# CAN_IF.net
KiCad netlist of a schematic drawn in Altium Designer
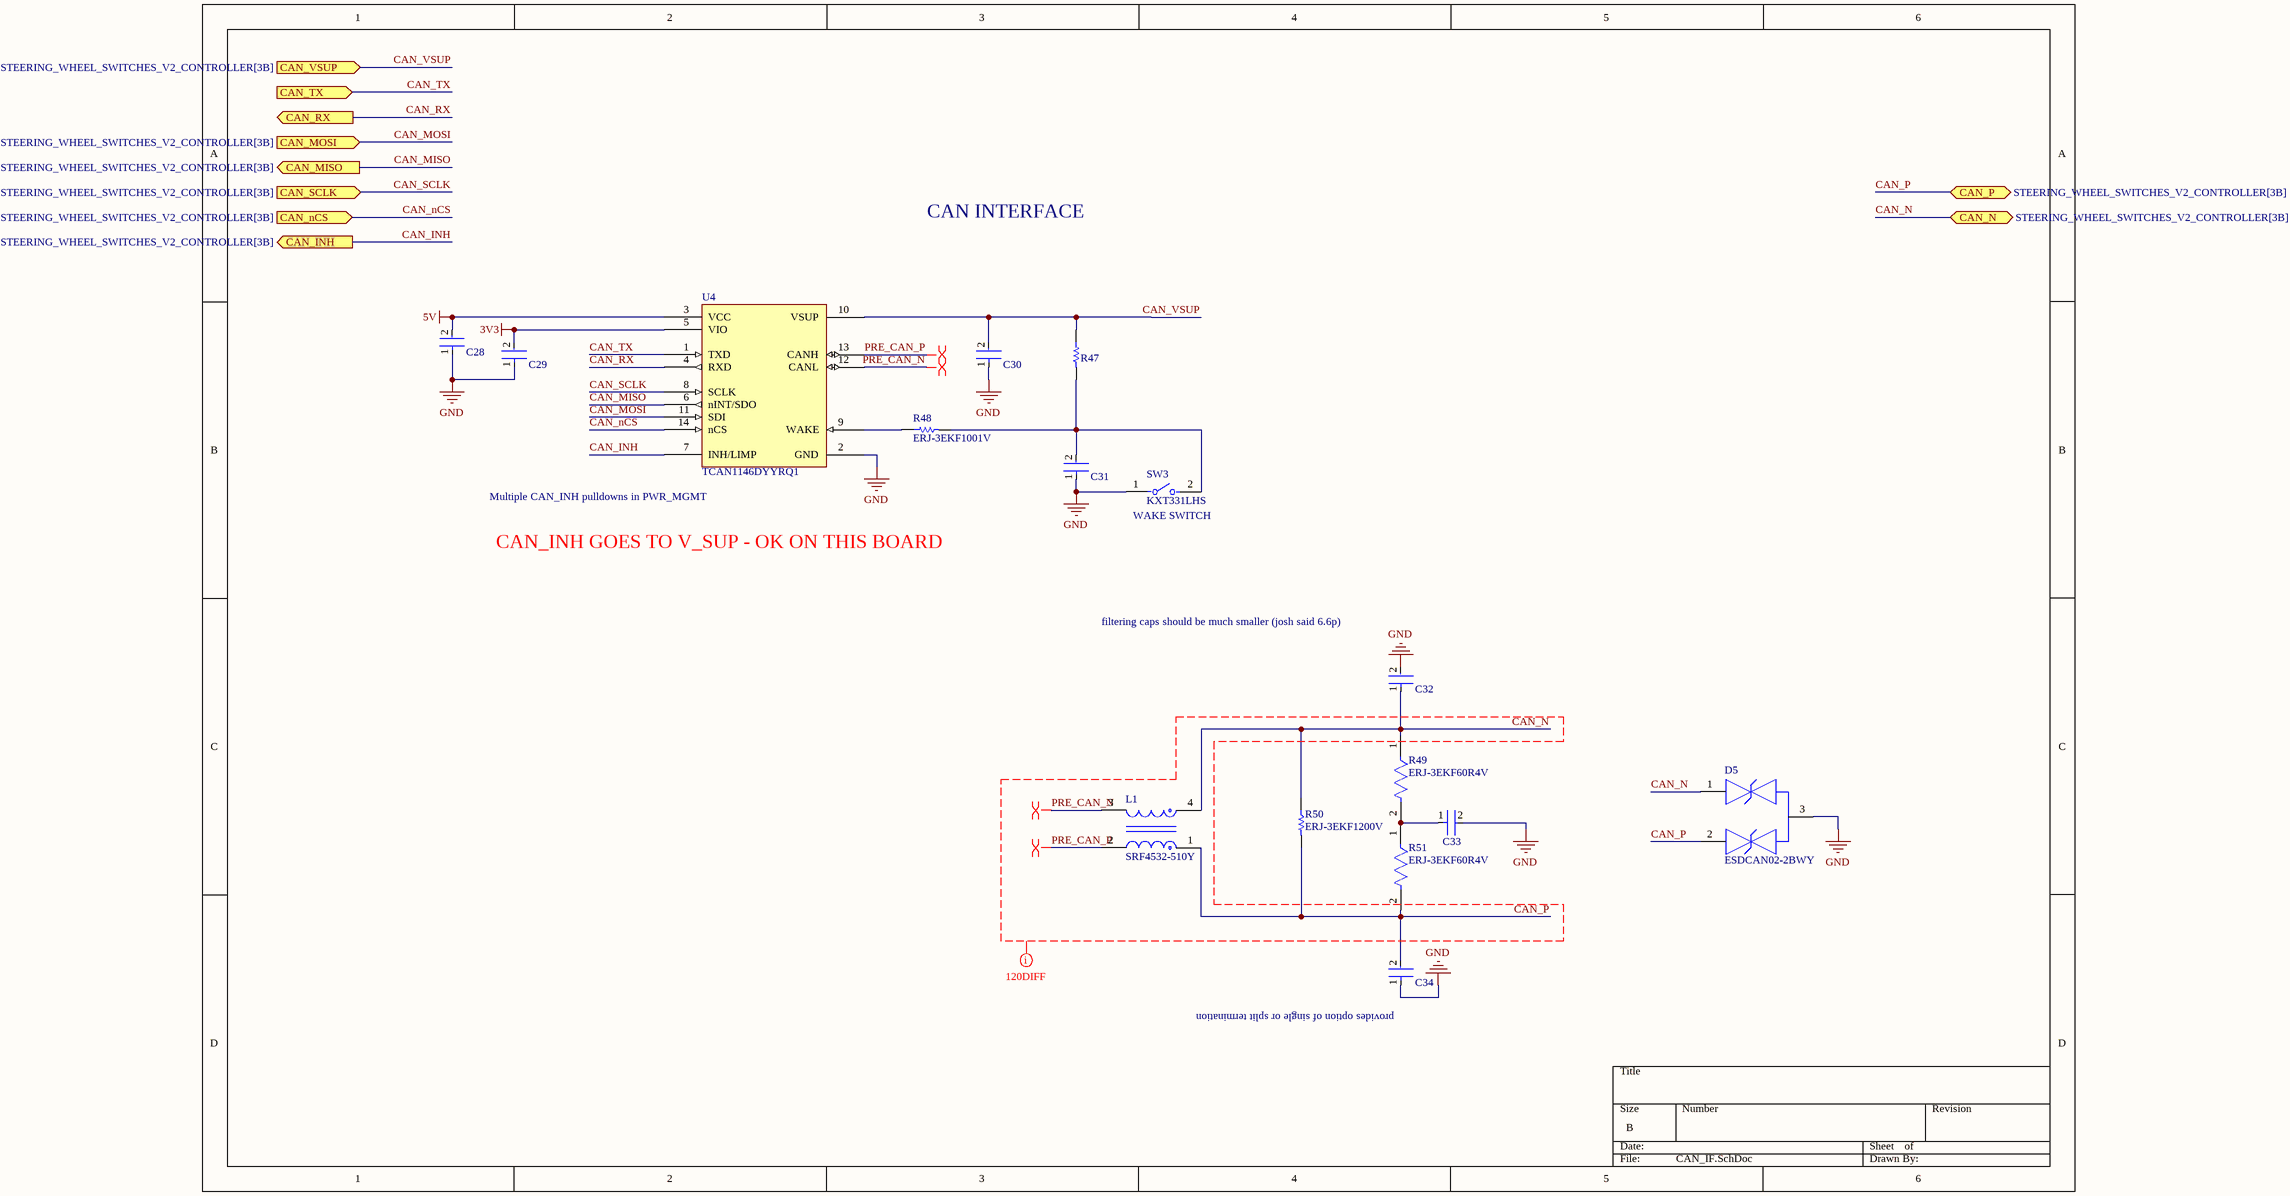
[diagram p0: CAN_IF.SchDoc]

(export (version "E")
  (design (tool "Eeschema 10.0.6"))
  (components
    (comp (ref "C28")
      (value "C0402C104K8PACTU")
      (footprint "FP-C0402-BB-MFG")
      (description "CAP CER 0.1UF 10V X5R 0402")
      (fields (field (name "MANUFACTURER") "Kemet") (field (name "TOLERANCE") "0.1"))
      (libsource (lib "Altium Content Vault") (part "b4654b650e69147ec39a6b967a45e02"))
    )
    (comp (ref "C29")
      (value "C0402C104K8PACTU")
      (footprint "FP-C0402-BB-MFG")
      (description "CAP CER 0.1UF 10V X5R 0402")
      (fields (field (name "MANUFACTURER") "Kemet") (field (name "TOLERANCE") "0.1"))
      (libsource (lib "Altium Content Vault") (part "b4654b650e69147ec39a6b967a45e02"))
    )
    (comp (ref "C30")
      (value "C0402C104K8PACTU")
      (footprint "FP-C0402-BB-MFG")
      (description "CAP CER 0.1UF 10V X5R 0402")
      (fields (field (name "MANUFACTURER") "Kemet") (field (name "TOLERANCE") "0.1"))
      (libsource (lib "Altium Content Vault") (part "b4654b650e69147ec39a6b967a45e02"))
    )
    (comp (ref "C31")
      (value "C0402C104K8PACTU")
      (footprint "FP-C0402-BB-MFG")
      (description "CAP CER 0.1UF 10V X5R 0402")
      (fields (field (name "MANUFACTURER") "Kemet") (field (name "TOLERANCE") "0.1"))
      (libsource (lib "Altium Content Vault") (part "b4654b650e69147ec39a6b967a45e02"))
    )
    (comp (ref "C32")
      (value "C0402C104K8PACTU")
      (footprint "FP-C0402-BB-MFG")
      (description "CAP CER 0.1UF 10V X5R 0402")
      (fields (field (name "MANUFACTURER") "Kemet") (field (name "TOLERANCE") "0.1"))
      (libsource (lib "Altium Content Vault") (part "b4654b650e69147ec39a6b967a45e02"))
    )
    (comp (ref "C33")
      (value "C0402C104K8PACTU")
      (footprint "FP-C0402-BB-MFG")
      (description "CAP CER 0.1UF 10V X5R 0402")
      (fields (field (name "MANUFACTURER") "Kemet") (field (name "TOLERANCE") "0.1"))
      (libsource (lib "Altium Content Vault") (part "b4654b650e69147ec39a6b967a45e02"))
    )
    (comp (ref "C34")
      (value "C0402C104K8PACTU")
      (footprint "FP-C0402-BB-MFG")
      (description "CAP CER 0.1UF 10V X5R 0402")
      (fields (field (name "MANUFACTURER") "Kemet") (field (name "TOLERANCE") "0.1"))
      (libsource (lib "Altium Content Vault") (part "b4654b650e69147ec39a6b967a45e02"))
    )
    (comp (ref "D5")
      (value "ESDCAN02-2BWY")
      (footprint "FP-SOT323-3L-MFG")
      (description "TVS DIODE 26.5V 44V SOT323-3")
      (fields
        (field (name "MANUFACTURER") "STMicroelectronics")
        (field (name "OCTOPART") "https://octopart.com/esdcan02-2bwy-stmicroelectronics-58631133")
      )
      (libsource (lib "Altium Content Vault") (part "0b9019fb5e52ed66df21ec1535be59d"))
    )
    (comp (ref "L1")
      (value "SRF4532-510Y")
      (footprint "FP-SRF4532-MFG")
      (description "CMC 51UH 200MA 2LN 2KOHM SMD")
      (fields (field (name "TOLERANCE") "50%"))
      (libsource (lib "Altium Content Vault") (part "aca3f6a10b859f211cca95010157f3b"))
    )
    (comp (ref "R47")
      (value "ERJ3EKF1002V")
      (footprint "RESC1609X55X30LL15T15")
      (description "Chip Resistor, 10 KOhm, +/- 1%, 0.1 W, -55 to 155 degC, 0603 (1608 Metric), RoHS, Tape and Reel")
      (fields (field (name "TOLERANCE") "1%") (field (name "MANUFACTURER") "Panasonic"))
      (libsource (lib "Altium Content Vault") (part "RES-2"))
    )
    (comp (ref "R48")
      (value "ERJ-3EKF1001V")
      (footprint "RESC1608X55X30LL15T15")
      (fields (field (name "MANUFACTURER") "Panasonic"))
      (libsource (lib "Altium Content Vault") (part "RES"))
    )
    (comp (ref "R49")
      (value "ERJ-3EKF60R4V")
      (footprint "FP-ERJ3EK-IPC_C")
      (description "RES SMD 60.4 OHM 1% 1/10W 0603")
      (fields (field (name "TOLERANCE") "1%"))
      (libsource (lib "Altium Content Vault") (part "1029c3af85768c4190bb7ad29bc67b5"))
    )
    (comp (ref "R50")
      (value "ERJ-3EKF1200V")
      (footprint "RESC1609X55X30ML15T15")
      (description "Chip Resistor, 120 Ohm, +/- 1%, 0.1 W, -55 to 155 degC, 0603 (1608 Metric), RoHS, Tape and Reel")
      (fields (field (name "TOLERANCE") "1%") (field (name "MANUFACTURER") "Panasonic"))
      (libsource (lib "Altium Content Vault") (part "RES-2"))
    )
    (comp (ref "R51")
      (value "ERJ-3EKF60R4V")
      (footprint "FP-ERJ3EK-IPC_C")
      (description "RES SMD 60.4 OHM 1% 1/10W 0603")
      (fields (field (name "TOLERANCE") "1%"))
      (libsource (lib "Altium Content Vault") (part "1029c3af85768c4190bb7ad29bc67b5"))
    )
    (comp (ref "SW3")
      (value "KXT331LHS")
      (footprint "FP-KXT331LHS-MFG")
      (description "SWITCH TACTILE SPST-NO 0.02A 15V")
      (libsource (lib "Altium Content Vault") (part "bb27bde45df87f1f469753f287ef5ae"))
    )
    (comp (ref "U4")
      (value "TCAN1146DYYRQ1")
      (footprint "TCAN1146DYYRQ1-Footprint-1")
      (libsource (lib "Space Concordia") (part "CMP-015-00012-2"))
    )
  )
  (nets
    (net (code "1") (name "/CAN_INH") (class "Default")
      (node (ref "U4") (pin "7") (pinfunction "INH/LIMP_7") (pintype "passive"))
    )
    (net (code "2") (name "/CAN_MISO") (class "Default")
      (node (ref "U4") (pin "6") (pinfunction "nINT/SDO_6") (pintype "output"))
    )
    (net (code "3") (name "/CAN_MOSI") (class "Default")
      (node (ref "U4") (pin "11") (pinfunction "SDI_11") (pintype "input"))
    )
    (net (code "4") (name "/CAN_N") (class "Default")
      (node (ref "C32") (pin "1") (pinfunction "1_1") (pintype "passive"))
      (node (ref "D5") (pin "1") (pinfunction "1_1") (pintype "passive"))
      (node (ref "L1") (pin "4") (pinfunction "4_4") (pintype "passive"))
      (node (ref "R49") (pin "1") (pinfunction "1_1") (pintype "passive"))
      (node (ref "R50") (pin "1") (pinfunction "1_1") (pintype "passive"))
    )
    (net (code "5") (name "/CAN_P") (class "Default")
      (node (ref "C34") (pin "2") (pinfunction "2_2") (pintype "passive"))
      (node (ref "D5") (pin "2") (pinfunction "2_2") (pintype "passive"))
      (node (ref "L1") (pin "1") (pinfunction "1_1") (pintype "passive"))
      (node (ref "R50") (pin "2") (pinfunction "2_2") (pintype "passive"))
      (node (ref "R51") (pin "2") (pinfunction "2_2") (pintype "passive"))
    )
    (net (code "6") (name "/CAN_RX") (class "Default")
      (node (ref "U4") (pin "4") (pinfunction "RXD_4") (pintype "output"))
    )
    (net (code "7") (name "/CAN_SCLK") (class "Default")
      (node (ref "U4") (pin "8") (pinfunction "SCLK_8") (pintype "input"))
    )
    (net (code "8") (name "/CAN_TX") (class "Default")
      (node (ref "U4") (pin "1") (pinfunction "TXD_1") (pintype "input"))
    )
    (net (code "9") (name "/CAN_VSUP") (class "Default")
      (node (ref "C30") (pin "2") (pinfunction "2_2") (pintype "passive"))
      (node (ref "R47") (pin "1") (pinfunction "1_1") (pintype "passive"))
      (node (ref "U4") (pin "10") (pinfunction "VSUP_10") (pintype "power_in"))
    )
    (net (code "10") (name "/CAN_nCS") (class "Default")
      (node (ref "U4") (pin "14") (pinfunction "nCS_14") (pintype "input"))
    )
    (net (code "11") (name "/PRE_CAN_N") (class "Default")
      (node (ref "L1") (pin "3") (pinfunction "3_3") (pintype "passive"))
      (node (ref "U4") (pin "12") (pinfunction "CANL_12") (pintype "bidirectional"))
    )
    (net (code "12") (name "/PRE_CAN_P") (class "Default")
      (node (ref "L1") (pin "2") (pinfunction "2_2") (pintype "passive"))
      (node (ref "U4") (pin "13") (pinfunction "CANH_13") (pintype "bidirectional"))
    )
    (net (code "13") (name "3V3") (class "Default")
      (node (ref "C29") (pin "2") (pinfunction "2_2") (pintype "passive"))
      (node (ref "U4") (pin "5") (pinfunction "VIO_5") (pintype "power_in"))
    )
    (net (code "14") (name "5V") (class "Default")
      (node (ref "C28") (pin "2") (pinfunction "2_2") (pintype "passive"))
      (node (ref "U4") (pin "3") (pinfunction "VCC_3") (pintype "power_in"))
    )
    (net (code "15") (name "GND") (class "Default")
      (node (ref "C28") (pin "1") (pinfunction "1_1") (pintype "passive"))
      (node (ref "C29") (pin "1") (pinfunction "1_1") (pintype "passive"))
      (node (ref "C30") (pin "1") (pinfunction "1_1") (pintype "passive"))
      (node (ref "C31") (pin "1") (pinfunction "1_1") (pintype "passive"))
      (node (ref "C32") (pin "2") (pinfunction "2_2") (pintype "passive"))
      (node (ref "C33") (pin "2") (pinfunction "2_2") (pintype "passive"))
      (node (ref "C34") (pin "1") (pinfunction "1_1") (pintype "passive"))
      (node (ref "D5") (pin "3") (pinfunction "3_3") (pintype "passive"))
      (node (ref "SW3") (pin "1") (pinfunction "1_1") (pintype "passive"))
      (node (ref "U4") (pin "2") (pinfunction "GND_2") (pintype "power_in"))
    )
    (net (code "16") (name "Net-(C31-Pad2)") (class "Default")
      (node (ref "C31") (pin "2") (pinfunction "2_2") (pintype "passive"))
      (node (ref "R47") (pin "2") (pinfunction "2_2") (pintype "passive"))
      (node (ref "R48") (pin "2") (pinfunction "2_2") (pintype "passive"))
      (node (ref "SW3") (pin "2") (pinfunction "2_2") (pintype "passive"))
    )
    (net (code "17") (name "Net-(C33-Pad1)") (class "Default")
      (node (ref "C33") (pin "1") (pinfunction "1_1") (pintype "passive"))
      (node (ref "R49") (pin "2") (pinfunction "2_2") (pintype "passive"))
      (node (ref "R51") (pin "1") (pinfunction "1_1") (pintype "passive"))
    )
    (net (code "18") (name "Net-(U4-WAKE)") (class "Default")
      (node (ref "R48") (pin "1") (pinfunction "1_1") (pintype "passive"))
      (node (ref "U4") (pin "9") (pinfunction "WAKE_9") (pintype "input"))
    )
  )
)
